# Kretsn_Brillz.net
KiCad netlist of a schematic drawn in Altium Designer
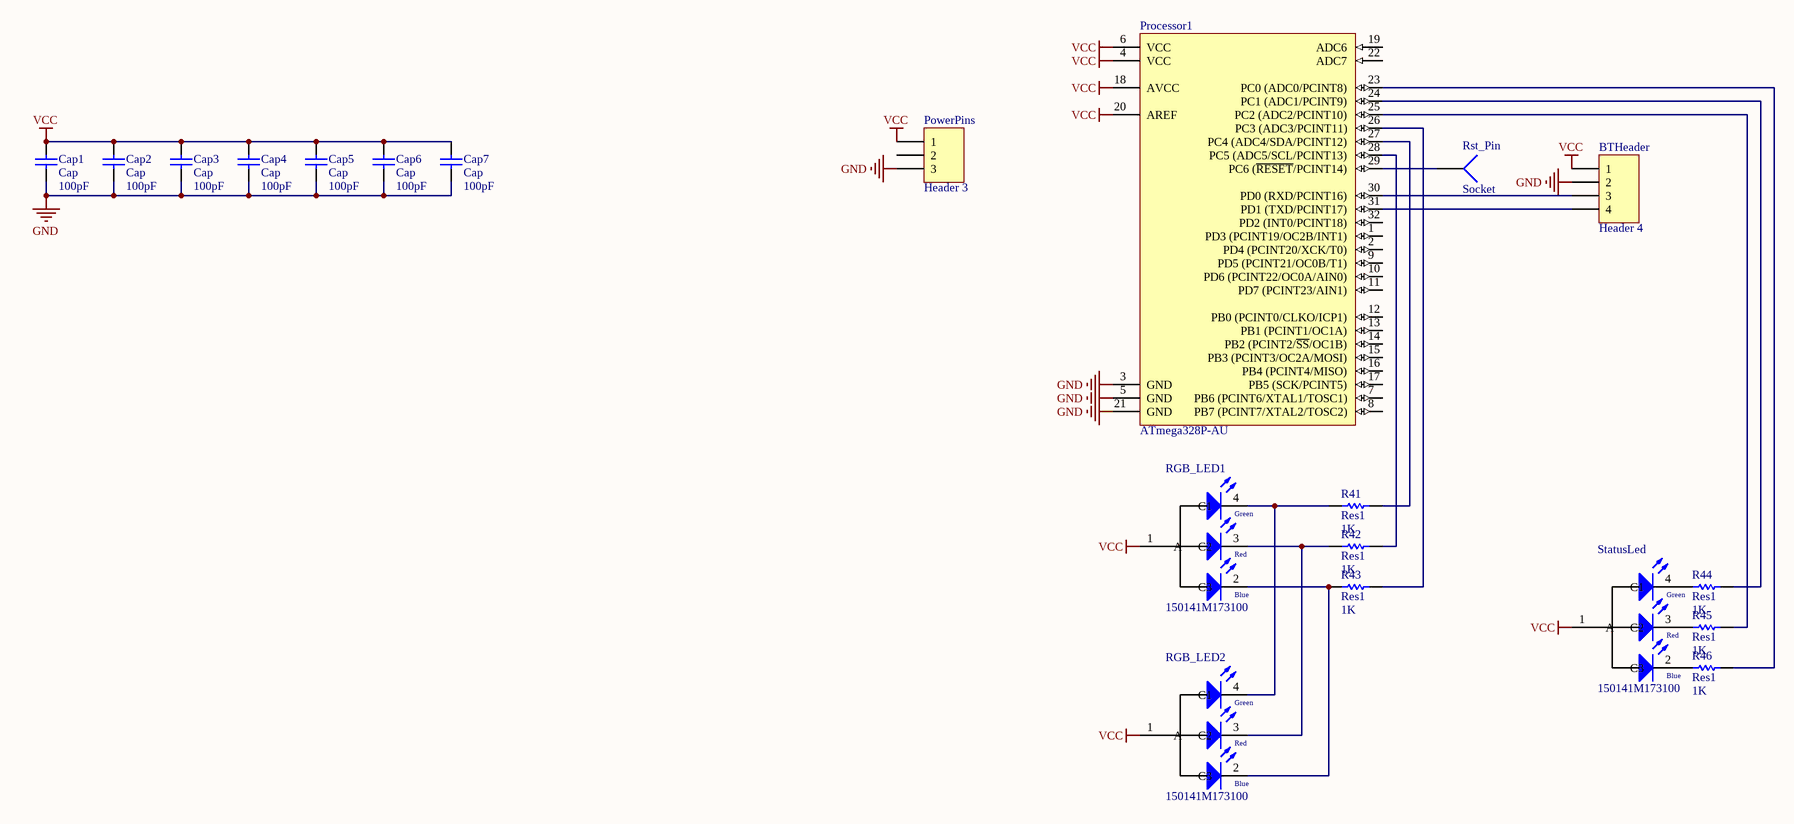
[diagram p0: Kretsn_Brillz.SchDoc]

(export (version "E")
  (design (tool "Eeschema 10.0.6"))
  (components
    (comp (ref "BTHeader")
      (value "Header 4")
      (footprint "HDR1X4")
      (description "Header, 4-Pin")
      (fields (field (name "PUBLISHER") "Altium Limited"))
      (libsource (lib "Miscellaneous Connectors") (part "Header 4"))
    )
    (comp (ref "Cap1")
      (value "Cap")
      (footprint "6-0805_N")
      (description "Capacitor")
      (fields (field (name "ALTIUM_VALUE") "100pF") (field (name "PUBLISHER") "Altium Limited"))
      (libsource (lib "Miscellaneous Devices") (part "Cap"))
    )
    (comp (ref "Cap2")
      (value "Cap")
      (footprint "6-0805_N")
      (description "Capacitor")
      (fields (field (name "ALTIUM_VALUE") "100pF") (field (name "PUBLISHER") "Altium Limited"))
      (libsource (lib "Miscellaneous Devices") (part "Cap"))
    )
    (comp (ref "Cap3")
      (value "Cap")
      (footprint "6-0805_N")
      (description "Capacitor")
      (fields (field (name "ALTIUM_VALUE") "100pF") (field (name "PUBLISHER") "Altium Limited"))
      (libsource (lib "Miscellaneous Devices") (part "Cap"))
    )
    (comp (ref "Cap4")
      (value "Cap")
      (footprint "6-0805_N")
      (description "Capacitor")
      (fields (field (name "ALTIUM_VALUE") "100pF") (field (name "PUBLISHER") "Altium Limited"))
      (libsource (lib "Miscellaneous Devices") (part "Cap"))
    )
    (comp (ref "Cap5")
      (value "Cap")
      (footprint "6-0805_N")
      (description "Capacitor")
      (fields (field (name "ALTIUM_VALUE") "100pF") (field (name "PUBLISHER") "Altium Limited"))
      (libsource (lib "Miscellaneous Devices") (part "Cap"))
    )
    (comp (ref "Cap6")
      (value "Cap")
      (footprint "6-0805_N")
      (description "Capacitor")
      (fields (field (name "ALTIUM_VALUE") "100pF") (field (name "PUBLISHER") "Altium Limited"))
      (libsource (lib "Miscellaneous Devices") (part "Cap"))
    )
    (comp (ref "Cap7")
      (value "Cap")
      (footprint "6-0805_N")
      (description "Capacitor")
      (fields (field (name "ALTIUM_VALUE") "100pF") (field (name "PUBLISHER") "Altium Limited"))
      (libsource (lib "Miscellaneous Devices") (part "Cap"))
    )
    (comp (ref "PowerPins")
      (value "Header 3")
      (footprint "HDR1X3")
      (description "Header, 3-Pin")
      (fields (field (name "PUBLISHER") "Altium Limited"))
      (libsource (lib "Miscellaneous Connectors") (part "Header 3"))
    )
    (comp (ref "Processor1")
      (value "ATmega328P-AU")
      (footprint "32A_N")
      (fields (field (name "PUBLISHER") "Altium Limited"))
      (libsource (lib "Atmel Microcontroller 8-Bit megaAVR") (part "ATmega328P-AU"))
    )
    (comp (ref "R41")
      (value "Res1")
      (description "Resistor")
      (fields (field (name "ALTIUM_VALUE") "1K") (field (name "PUBLISHER") "Altium Limited"))
      (libsource (lib "Miscellaneous Devices") (part "Res1"))
    )
    (comp (ref "R42")
      (value "Res1")
      (description "Resistor")
      (fields (field (name "ALTIUM_VALUE") "1K") (field (name "PUBLISHER") "Altium Limited"))
      (libsource (lib "Miscellaneous Devices") (part "Res1"))
    )
    (comp (ref "R43")
      (value "Res1")
      (description "Resistor")
      (fields (field (name "ALTIUM_VALUE") "1K") (field (name "PUBLISHER") "Altium Limited"))
      (libsource (lib "Miscellaneous Devices") (part "Res1"))
    )
    (comp (ref "R44")
      (value "Res1")
      (description "Resistor")
      (fields (field (name "ALTIUM_VALUE") "1K") (field (name "PUBLISHER") "Altium Limited"))
      (libsource (lib "Miscellaneous Devices") (part "Res1"))
    )
    (comp (ref "R45")
      (value "Res1")
      (description "Resistor")
      (fields (field (name "ALTIUM_VALUE") "1K") (field (name "PUBLISHER") "Altium Limited"))
      (libsource (lib "Miscellaneous Devices") (part "Res1"))
    )
    (comp (ref "R46")
      (value "Res1")
      (description "Resistor")
      (fields (field (name "ALTIUM_VALUE") "1K") (field (name "PUBLISHER") "Altium Limited"))
      (libsource (lib "Miscellaneous Devices") (part "Res1"))
    )
    (comp (ref "RGB_LED1")
      (value "150141M173100")
      (footprint "3528")
      (description "SMD Full-Color Top LED, WL-SFTW, Red & Green & Blue")
      (fields
        (field (name "MANUFACTURER") "Würth Elektronik eiSos GmbH")
        (field (name "CREATED BY") "Christin Otto")
      )
      (libsource (lib "WL-SFTW_rev15a") (part "WL-SFTW 3528 150141M173100"))
    )
    (comp (ref "RGB_LED2")
      (value "150141M173100")
      (footprint "3528")
      (description "SMD Full-Color Top LED, WL-SFTW, Red & Green & Blue")
      (fields
        (field (name "MANUFACTURER") "Würth Elektronik eiSos GmbH")
        (field (name "CREATED BY") "Christin Otto")
      )
      (libsource (lib "WL-SFTW_rev15a") (part "WL-SFTW 3528 150141M173100"))
    )
    (comp (ref "Rst_Pin")
      (value "Socket")
      (footprint "PIN1")
      (fields (field (name "PUBLISHER") "Altium Limited"))
      (libsource (lib "Miscellaneous Connectors") (part "Socket"))
    )
    (comp (ref "StatusLed")
      (value "150141M173100")
      (footprint "3528")
      (description "SMD Full-Color Top LED, WL-SFTW, Red & Green & Blue")
      (fields
        (field (name "MANUFACTURER") "Würth Elektronik eiSos GmbH")
        (field (name "CREATED BY") "Christin Otto")
      )
      (libsource (lib "WL-SFTW_rev15a") (part "WL-SFTW 3528 150141M173100"))
    )
  )
  (nets
    (net (code "1") (name "GND") (class "Default")
      (node (ref "BTHeader") (pin "2") (pinfunction "2_2") (pintype "passive"))
      (node (ref "Cap1") (pin "1") (pinfunction "1_1") (pintype "passive"))
      (node (ref "Cap2") (pin "1") (pinfunction "1_1") (pintype "passive"))
      (node (ref "Cap3") (pin "1") (pinfunction "1_1") (pintype "passive"))
      (node (ref "Cap4") (pin "2") (pinfunction "2_2") (pintype "passive"))
      (node (ref "Cap5") (pin "2") (pinfunction "2_2") (pintype "passive"))
      (node (ref "Cap6") (pin "2") (pinfunction "2_2") (pintype "passive"))
      (node (ref "Cap7") (pin "2") (pinfunction "2_2") (pintype "passive"))
      (node (ref "PowerPins") (pin "3") (pinfunction "3_3") (pintype "passive"))
      (node (ref "Processor1") (pin "21") (pinfunction "GND_21") (pintype "power_in"))
      (node (ref "Processor1") (pin "3") (pinfunction "GND_3") (pintype "power_in"))
      (node (ref "Processor1") (pin "5") (pinfunction "GND_5") (pintype "power_in"))
    )
    (net (code "2") (name "Net-(Processor1-PC0_(ADC0{slash}PCINT8))") (class "Default")
      (node (ref "Processor1") (pin "23") (pinfunction "PC0_(ADC0/PCINT8)_23") (pintype "bidirectional"))
      (node (ref "R46") (pin "2") (pinfunction "2_2") (pintype "passive"))
    )
    (net (code "3") (name "Net-(Processor1-PC1_(ADC1{slash}PCINT9))") (class "Default")
      (node (ref "Processor1") (pin "24") (pinfunction "PC1_(ADC1/PCINT9)_24") (pintype "bidirectional"))
      (node (ref "R44") (pin "2") (pinfunction "2_2") (pintype "passive"))
    )
    (net (code "4") (name "Net-(Processor1-PC2_(ADC2{slash}PCINT10))") (class "Default")
      (node (ref "Processor1") (pin "25") (pinfunction "PC2_(ADC2/PCINT10)_25") (pintype "bidirectional"))
      (node (ref "R45") (pin "2") (pinfunction "2_2") (pintype "passive"))
    )
    (net (code "5") (name "Net-(Processor1-PC3_(ADC3{slash}PCINT11))") (class "Default")
      (node (ref "Processor1") (pin "26") (pinfunction "PC3_(ADC3/PCINT11)_26") (pintype "bidirectional"))
      (node (ref "R43") (pin "2") (pinfunction "2_2") (pintype "passive"))
    )
    (net (code "6") (name "Net-(Processor1-PC4_(ADC4{slash}SDA{slash}PCINT12))") (class "Default")
      (node (ref "Processor1") (pin "27") (pinfunction "PC4_(ADC4/SDA/PCINT12)_27") (pintype "bidirectional"))
      (node (ref "R41") (pin "2") (pinfunction "2_2") (pintype "passive"))
    )
    (net (code "7") (name "Net-(Processor1-PC5_(ADC5{slash}SCL{slash}PCINT13))") (class "Default")
      (node (ref "Processor1") (pin "28") (pinfunction "PC5_(ADC5/SCL/PCINT13)_28") (pintype "bidirectional"))
      (node (ref "R42") (pin "2") (pinfunction "2_2") (pintype "passive"))
    )
    (net (code "8") (name "Net-(Processor1-PC6_(~{RESET}{slash}PCINT14))") (class "Default")
      (node (ref "Processor1") (pin "29") (pinfunction "PC6_(~{RESET}/PCINT14)_29") (pintype "bidirectional"))
      (node (ref "Rst_Pin") (pin "1") (pinfunction "1_1") (pintype "passive"))
    )
    (net (code "9") (name "Net-(Processor1-PD0_(RXD{slash}PCINT16))") (class "Default")
      (node (ref "BTHeader") (pin "3") (pinfunction "3_3") (pintype "passive"))
      (node (ref "Processor1") (pin "30") (pinfunction "PD0_(RXD/PCINT16)_30") (pintype "bidirectional"))
    )
    (net (code "10") (name "Net-(Processor1-PD1_(TXD{slash}PCINT17))") (class "Default")
      (node (ref "BTHeader") (pin "4") (pinfunction "4_4") (pintype "passive"))
      (node (ref "Processor1") (pin "31") (pinfunction "PD1_(TXD/PCINT17)_31") (pintype "bidirectional"))
    )
    (net (code "11") (name "Net-(RGB_LED1-C1)") (class "Default")
      (node (ref "R41") (pin "1") (pinfunction "1_1") (pintype "passive"))
      (node (ref "RGB_LED1") (pin "4") (pinfunction "C1_4") (pintype "passive"))
      (node (ref "RGB_LED2") (pin "4") (pinfunction "C1_4") (pintype "passive"))
    )
    (net (code "12") (name "Net-(RGB_LED1-C2)") (class "Default")
      (node (ref "R42") (pin "1") (pinfunction "1_1") (pintype "passive"))
      (node (ref "RGB_LED1") (pin "3") (pinfunction "C2_3") (pintype "passive"))
      (node (ref "RGB_LED2") (pin "3") (pinfunction "C2_3") (pintype "passive"))
    )
    (net (code "13") (name "Net-(RGB_LED1-C3)") (class "Default")
      (node (ref "R43") (pin "1") (pinfunction "1_1") (pintype "passive"))
      (node (ref "RGB_LED1") (pin "2") (pinfunction "C3_2") (pintype "passive"))
      (node (ref "RGB_LED2") (pin "2") (pinfunction "C3_2") (pintype "passive"))
    )
    (net (code "14") (name "Net-(StatusLed-C1)") (class "Default")
      (node (ref "R44") (pin "1") (pinfunction "1_1") (pintype "passive"))
      (node (ref "StatusLed") (pin "4") (pinfunction "C1_4") (pintype "passive"))
    )
    (net (code "15") (name "Net-(StatusLed-C2)") (class "Default")
      (node (ref "R45") (pin "1") (pinfunction "1_1") (pintype "passive"))
      (node (ref "StatusLed") (pin "3") (pinfunction "C2_3") (pintype "passive"))
    )
    (net (code "16") (name "Net-(StatusLed-C3)") (class "Default")
      (node (ref "R46") (pin "1") (pinfunction "1_1") (pintype "passive"))
      (node (ref "StatusLed") (pin "2") (pinfunction "C3_2") (pintype "passive"))
    )
    (net (code "17") (name "VCC") (class "Default")
      (node (ref "BTHeader") (pin "1") (pinfunction "1_1") (pintype "passive"))
      (node (ref "Cap1") (pin "2") (pinfunction "2_2") (pintype "passive"))
      (node (ref "Cap2") (pin "2") (pinfunction "2_2") (pintype "passive"))
      (node (ref "Cap3") (pin "2") (pinfunction "2_2") (pintype "passive"))
      (node (ref "Cap4") (pin "1") (pinfunction "1_1") (pintype "passive"))
      (node (ref "Cap5") (pin "1") (pinfunction "1_1") (pintype "passive"))
      (node (ref "Cap6") (pin "1") (pinfunction "1_1") (pintype "passive"))
      (node (ref "Cap7") (pin "1") (pinfunction "1_1") (pintype "passive"))
      (node (ref "PowerPins") (pin "1") (pinfunction "1_1") (pintype "passive"))
      (node (ref "Processor1") (pin "18") (pinfunction "AVCC_18") (pintype "power_in"))
      (node (ref "Processor1") (pin "20") (pinfunction "AREF_20") (pintype "passive"))
      (node (ref "Processor1") (pin "4") (pinfunction "VCC_4") (pintype "power_in"))
      (node (ref "Processor1") (pin "6") (pinfunction "VCC_6") (pintype "power_in"))
      (node (ref "RGB_LED1") (pin "1") (pinfunction "A_1") (pintype "passive"))
      (node (ref "RGB_LED2") (pin "1") (pinfunction "A_1") (pintype "passive"))
      (node (ref "StatusLed") (pin "1") (pinfunction "A_1") (pintype "passive"))
    )
    (net (code "18") (name "unconnected-(PowerPins-Pad2)") (class "Default")
      (node (ref "PowerPins") (pin "2") (pinfunction "2_2") (pintype "passive"))
    )
    (net (code "19") (name "unconnected-(Processor1-ADC6-Pad19)") (class "Default")
      (node (ref "Processor1") (pin "19") (pinfunction "ADC6_19") (pintype "input"))
    )
    (net (code "20") (name "unconnected-(Processor1-ADC7-Pad22)") (class "Default")
      (node (ref "Processor1") (pin "22") (pinfunction "ADC7_22") (pintype "input"))
    )
    (net (code "21") (name "unconnected-(Processor1-PB0_(PCINT0{slash}CLKO{slash}ICP1)-Pad12)") (class "Default")
      (node (ref "Processor1") (pin "12") (pinfunction "PB0_(PCINT0/CLKO/ICP1)_12") (pintype "bidirectional"))
    )
    (net (code "22") (name "unconnected-(Processor1-PB1_(PCINT1{slash}OC1A)-Pad13)") (class "Default")
      (node (ref "Processor1") (pin "13") (pinfunction "PB1_(PCINT1/OC1A)_13") (pintype "bidirectional"))
    )
    (net (code "23") (name "unconnected-(Processor1-PB2_(PCINT2{slash}~{SS}{slash}OC1B)-Pad14)") (class "Default")
      (node (ref "Processor1") (pin "14") (pinfunction "PB2_(PCINT2/~{SS}/OC1B)_14") (pintype "bidirectional"))
    )
    (net (code "24") (name "unconnected-(Processor1-PB3_(PCINT3{slash}OC2A{slash}MOSI)-Pad15)") (class "Default")
      (node (ref "Processor1") (pin "15") (pinfunction "PB3_(PCINT3/OC2A/MOSI)_15") (pintype "bidirectional"))
    )
    (net (code "25") (name "unconnected-(Processor1-PB4_(PCINT4{slash}MISO)-Pad16)") (class "Default")
      (node (ref "Processor1") (pin "16") (pinfunction "PB4_(PCINT4/MISO)_16") (pintype "bidirectional"))
    )
    (net (code "26") (name "unconnected-(Processor1-PB5_(SCK{slash}PCINT5)-Pad17)") (class "Default")
      (node (ref "Processor1") (pin "17") (pinfunction "PB5_(SCK/PCINT5)_17") (pintype "bidirectional"))
    )
    (net (code "27") (name "unconnected-(Processor1-PB6_(PCINT6{slash}XTAL1{slash}TOSC1)-Pad7)") (class "Default")
      (node (ref "Processor1") (pin "7") (pinfunction "PB6_(PCINT6/XTAL1/TOSC1)_7") (pintype "bidirectional"))
    )
    (net (code "28") (name "unconnected-(Processor1-PB7_(PCINT7{slash}XTAL2{slash}TOSC2)-Pad8)") (class "Default")
      (node (ref "Processor1") (pin "8") (pinfunction "PB7_(PCINT7/XTAL2/TOSC2)_8") (pintype "bidirectional"))
    )
    (net (code "29") (name "unconnected-(Processor1-PD2_(INT0{slash}PCINT18)-Pad32)") (class "Default")
      (node (ref "Processor1") (pin "32") (pinfunction "PD2_(INT0/PCINT18)_32") (pintype "bidirectional"))
    )
    (net (code "30") (name "unconnected-(Processor1-PD3_(PCINT19{slash}OC2B{slash}INT1)-Pad1)") (class "Default")
      (node (ref "Processor1") (pin "1") (pinfunction "PD3_(PCINT19/OC2B/INT1)_1") (pintype "bidirectional"))
    )
    (net (code "31") (name "unconnected-(Processor1-PD4_(PCINT20{slash}XCK{slash}T0)-Pad2)") (class "Default")
      (node (ref "Processor1") (pin "2") (pinfunction "PD4_(PCINT20/XCK/T0)_2") (pintype "bidirectional"))
    )
    (net (code "32") (name "unconnected-(Processor1-PD5_(PCINT21{slash}OC0B{slash}T1)-Pad9)") (class "Default")
      (node (ref "Processor1") (pin "9") (pinfunction "PD5_(PCINT21/OC0B/T1)_9") (pintype "bidirectional"))
    )
    (net (code "33") (name "unconnected-(Processor1-PD6_(PCINT22{slash}OC0A{slash}AIN0)-Pad10)") (class "Default")
      (node (ref "Processor1") (pin "10") (pinfunction "PD6_(PCINT22/OC0A/AIN0)_10") (pintype "bidirectional"))
    )
    (net (code "34") (name "unconnected-(Processor1-PD7_(PCINT23{slash}AIN1)-Pad11)") (class "Default")
      (node (ref "Processor1") (pin "11") (pinfunction "PD7_(PCINT23/AIN1)_11") (pintype "bidirectional"))
    )
  )
)
